# Power_Stage.net
KiCad netlist of a schematic drawn in Altium Designer
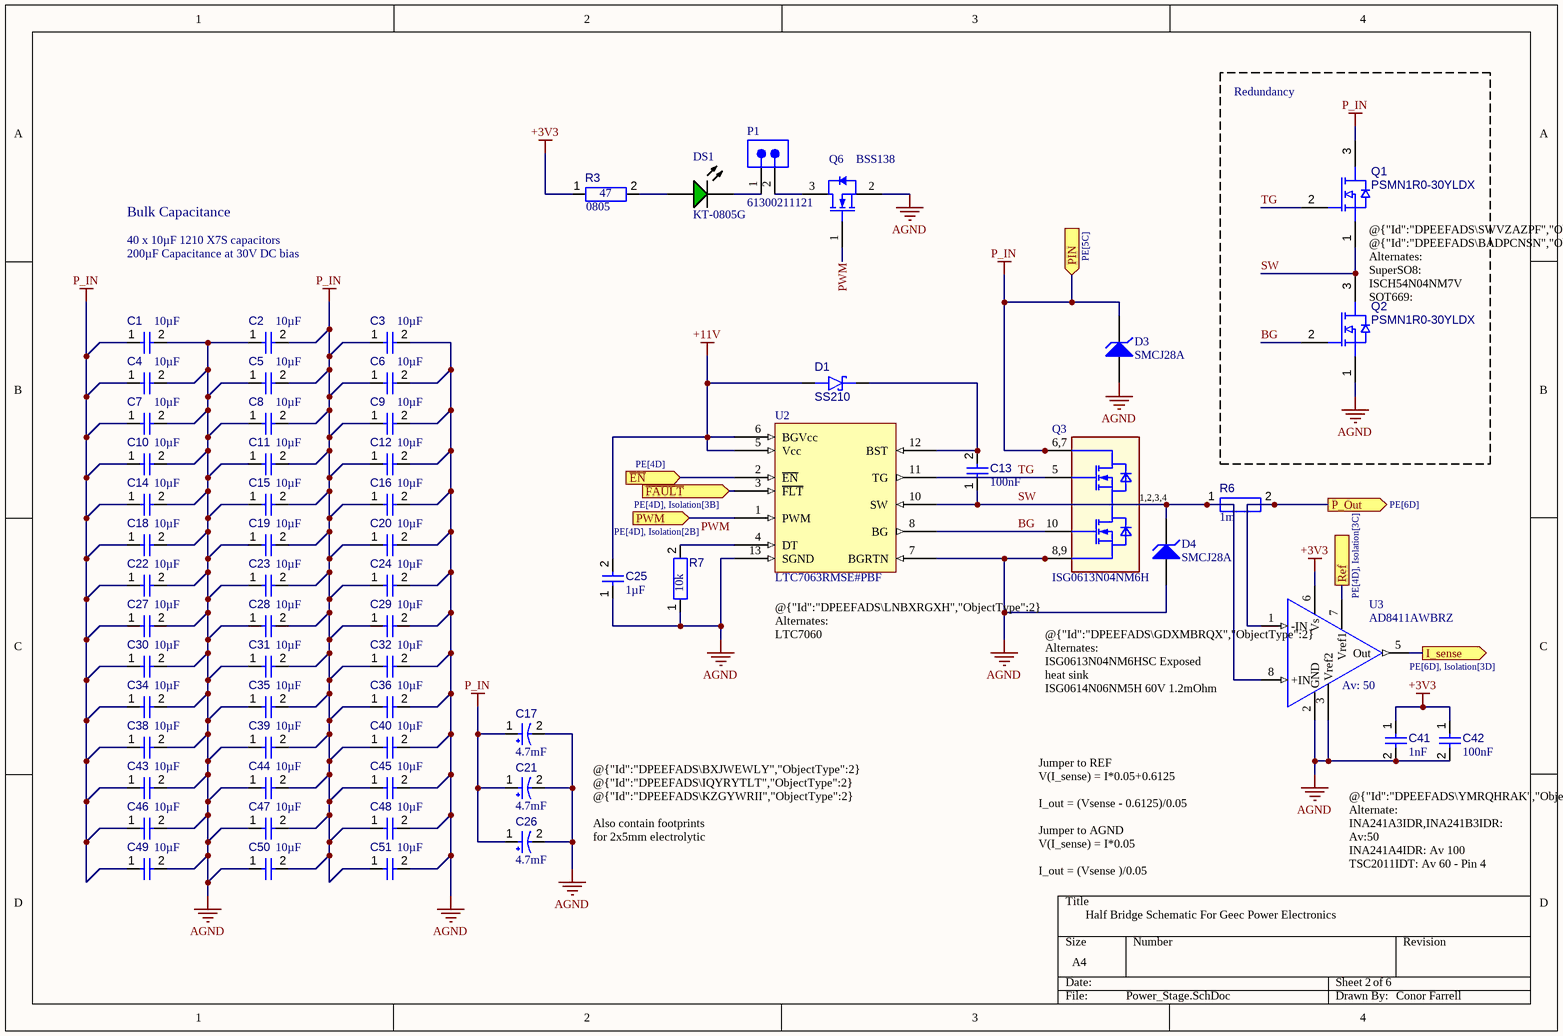
[diagram p0: Power_Stage.SchDoc]

(export (version "E")
  (design (tool "Eeschema 10.0.6"))
  (components
    (comp (ref "C1")
      (value "10µF")
      (footprint "FP-GCM32E-0_3-IPC_C")
      (description "50V 10uF X7S ±10% 1210 Multilayer Ceramic Capacitors MLCC - SMD/SMT ROHS")
      (fields (field (name "TOLERANCE") "10%") (field (name "Comment") "GCM32EC71H106KA03L"))
      (libsource (lib "University of Galway") (part "CAP-NP-2"))
    )
    (comp (ref "C2")
      (value "10µF")
      (footprint "FP-GCM32E-0_3-IPC_C")
      (description "50V 10uF X7S ±10% 1210 Multilayer Ceramic Capacitors MLCC - SMD/SMT ROHS")
      (fields (field (name "TOLERANCE") "10%") (field (name "Comment") "GCM32EC71H106KA03L"))
      (libsource (lib "University of Galway") (part "CAP-NP-2"))
    )
    (comp (ref "C3")
      (value "10µF")
      (footprint "FP-GCM32E-0_3-IPC_C")
      (description "50V 10uF X7S ±10% 1210 Multilayer Ceramic Capacitors MLCC - SMD/SMT ROHS")
      (fields (field (name "TOLERANCE") "10%") (field (name "Comment") "GCM32EC71H106KA03L"))
      (libsource (lib "University of Galway") (part "CAP-NP-2"))
    )
    (comp (ref "C4")
      (value "10µF")
      (footprint "FP-GCM32E-0_3-IPC_C")
      (description "50V 10uF X7S ±10% 1210 Multilayer Ceramic Capacitors MLCC - SMD/SMT ROHS")
      (fields (field (name "TOLERANCE") "10%") (field (name "Comment") "GCM32EC71H106KA03L"))
      (libsource (lib "University of Galway") (part "CAP-NP-2"))
    )
    (comp (ref "C5")
      (value "10µF")
      (footprint "FP-GCM32E-0_3-IPC_C")
      (description "50V 10uF X7S ±10% 1210 Multilayer Ceramic Capacitors MLCC - SMD/SMT ROHS")
      (fields (field (name "TOLERANCE") "10%") (field (name "Comment") "GCM32EC71H106KA03L"))
      (libsource (lib "University of Galway") (part "CAP-NP-2"))
    )
    (comp (ref "C6")
      (value "10µF")
      (footprint "FP-GCM32E-0_3-IPC_C")
      (description "50V 10uF X7S ±10% 1210 Multilayer Ceramic Capacitors MLCC - SMD/SMT ROHS")
      (fields (field (name "TOLERANCE") "10%") (field (name "Comment") "GCM32EC71H106KA03L"))
      (libsource (lib "University of Galway") (part "CAP-NP-2"))
    )
    (comp (ref "C7")
      (value "10µF")
      (footprint "FP-GCM32E-0_3-IPC_C")
      (description "50V 10uF X7S ±10% 1210 Multilayer Ceramic Capacitors MLCC - SMD/SMT ROHS")
      (fields (field (name "TOLERANCE") "10%") (field (name "Comment") "GCM32EC71H106KA03L"))
      (libsource (lib "University of Galway") (part "CAP-NP-2"))
    )
    (comp (ref "C8")
      (value "10µF")
      (footprint "FP-GCM32E-0_3-IPC_C")
      (description "50V 10uF X7S ±10% 1210 Multilayer Ceramic Capacitors MLCC - SMD/SMT ROHS")
      (fields (field (name "TOLERANCE") "10%") (field (name "Comment") "GCM32EC71H106KA03L"))
      (libsource (lib "University of Galway") (part "CAP-NP-2"))
    )
    (comp (ref "C9")
      (value "10µF")
      (footprint "FP-GCM32E-0_3-IPC_C")
      (description "50V 10uF X7S ±10% 1210 Multilayer Ceramic Capacitors MLCC - SMD/SMT ROHS")
      (fields (field (name "TOLERANCE") "10%") (field (name "Comment") "GCM32EC71H106KA03L"))
      (libsource (lib "University of Galway") (part "CAP-NP-2"))
    )
    (comp (ref "C10")
      (value "10µF")
      (footprint "FP-GCM32E-0_3-IPC_C")
      (description "50V 10uF X7S ±10% 1210 Multilayer Ceramic Capacitors MLCC - SMD/SMT ROHS")
      (fields (field (name "TOLERANCE") "10%") (field (name "Comment") "GCM32EC71H106KA03L"))
      (libsource (lib "University of Galway") (part "CAP-NP-2"))
    )
    (comp (ref "C11")
      (value "10µF")
      (footprint "FP-GCM32E-0_3-IPC_C")
      (description "50V 10uF X7S ±10% 1210 Multilayer Ceramic Capacitors MLCC - SMD/SMT ROHS")
      (fields (field (name "TOLERANCE") "10%") (field (name "Comment") "GCM32EC71H106KA03L"))
      (libsource (lib "University of Galway") (part "CAP-NP-2"))
    )
    (comp (ref "C12")
      (value "10µF")
      (footprint "FP-GCM32E-0_3-IPC_C")
      (description "50V 10uF X7S ±10% 1210 Multilayer Ceramic Capacitors MLCC - SMD/SMT ROHS")
      (fields (field (name "TOLERANCE") "10%") (field (name "Comment") "GCM32EC71H106KA03L"))
      (libsource (lib "University of Galway") (part "CAP-NP-2"))
    )
    (comp (ref "C13")
      (value "100nF")
      (footprint "CAPC3216X06N")
      (description "Ceramic Capacitor, Multilayer, Ceramic, 200V, 10% +Tol, 10% -Tol, X7R, 15% TC, 0.01uF, 1206")
      (fields (field (name "TOLERANCE") "10%") (field (name "Comment") "C1206C104K1RACTU"))
      (libsource (lib "University of Galway") (part "CAP-NP-2"))
    )
    (comp (ref "C14")
      (value "10µF")
      (footprint "FP-GCM32E-0_3-IPC_C")
      (description "50V 10uF X7S ±10% 1210 Multilayer Ceramic Capacitors MLCC - SMD/SMT ROHS")
      (fields (field (name "TOLERANCE") "10%") (field (name "Comment") "GCM32EC71H106KA03L"))
      (libsource (lib "University of Galway") (part "CAP-NP-2"))
    )
    (comp (ref "C15")
      (value "10µF")
      (footprint "FP-GCM32E-0_3-IPC_C")
      (description "50V 10uF X7S ±10% 1210 Multilayer Ceramic Capacitors MLCC - SMD/SMT ROHS")
      (fields (field (name "TOLERANCE") "10%") (field (name "Comment") "GCM32EC71H106KA03L"))
      (libsource (lib "University of Galway") (part "CAP-NP-2"))
    )
    (comp (ref "C16")
      (value "10µF")
      (footprint "FP-GCM32E-0_3-IPC_C")
      (description "50V 10uF X7S ±10% 1210 Multilayer Ceramic Capacitors MLCC - SMD/SMT ROHS")
      (fields (field (name "TOLERANCE") "10%") (field (name "Comment") "GCM32EC71H106KA03L"))
      (libsource (lib "University of Galway") (part "CAP-NP-2"))
    )
    (comp (ref "C17")
      (value "4.7mF")
      (footprint "UVR1J472MRD-Footprint-1")
      (description "Radial Can ALUMINUM ELECTROLYTIC CAPACITOR UVR 63V 4700muF ±20% 0.866Dia 22.00mm")
      (fields (field (name "TOLERANCE") "20%") (field (name "Comment") "UVR1J472MRD"))
      (libsource (lib "University of Galway") (part "CAP-P-2"))
    )
    (comp (ref "C18")
      (value "10µF")
      (footprint "FP-GCM32E-0_3-IPC_C")
      (description "50V 10uF X7S ±10% 1210 Multilayer Ceramic Capacitors MLCC - SMD/SMT ROHS")
      (fields (field (name "TOLERANCE") "10%") (field (name "Comment") "GCM32EC71H106KA03L"))
      (libsource (lib "University of Galway") (part "CAP-NP-2"))
    )
    (comp (ref "C19")
      (value "10µF")
      (footprint "FP-GCM32E-0_3-IPC_C")
      (description "50V 10uF X7S ±10% 1210 Multilayer Ceramic Capacitors MLCC - SMD/SMT ROHS")
      (fields (field (name "TOLERANCE") "10%") (field (name "Comment") "GCM32EC71H106KA03L"))
      (libsource (lib "University of Galway") (part "CAP-NP-2"))
    )
    (comp (ref "C20")
      (value "10µF")
      (footprint "FP-GCM32E-0_3-IPC_C")
      (description "50V 10uF X7S ±10% 1210 Multilayer Ceramic Capacitors MLCC - SMD/SMT ROHS")
      (fields (field (name "TOLERANCE") "10%") (field (name "Comment") "GCM32EC71H106KA03L"))
      (libsource (lib "University of Galway") (part "CAP-NP-2"))
    )
    (comp (ref "C21")
      (value "4.7mF")
      (footprint "UVR1J472MRD-Footprint-1")
      (description "Radial Can ALUMINUM ELECTROLYTIC CAPACITOR UVR 63V 4700muF ±20% 0.866Dia 22.00mm")
      (fields (field (name "TOLERANCE") "20%") (field (name "Comment") "UVR1J472MRD"))
      (libsource (lib "University of Galway") (part "CAP-P-2"))
    )
    (comp (ref "C22")
      (value "10µF")
      (footprint "FP-GCM32E-0_3-IPC_C")
      (description "50V 10uF X7S ±10% 1210 Multilayer Ceramic Capacitors MLCC - SMD/SMT ROHS")
      (fields (field (name "TOLERANCE") "10%") (field (name "Comment") "GCM32EC71H106KA03L"))
      (libsource (lib "University of Galway") (part "CAP-NP-2"))
    )
    (comp (ref "C23")
      (value "10µF")
      (footprint "FP-GCM32E-0_3-IPC_C")
      (description "50V 10uF X7S ±10% 1210 Multilayer Ceramic Capacitors MLCC - SMD/SMT ROHS")
      (fields (field (name "TOLERANCE") "10%") (field (name "Comment") "GCM32EC71H106KA03L"))
      (libsource (lib "University of Galway") (part "CAP-NP-2"))
    )
    (comp (ref "C24")
      (value "10µF")
      (footprint "FP-GCM32E-0_3-IPC_C")
      (description "50V 10uF X7S ±10% 1210 Multilayer Ceramic Capacitors MLCC - SMD/SMT ROHS")
      (fields (field (name "TOLERANCE") "10%") (field (name "Comment") "GCM32EC71H106KA03L"))
      (libsource (lib "University of Galway") (part "CAP-NP-2"))
    )
    (comp (ref "C25")
      (value "1µF")
      (footprint "CAPC3216X180X20ML20")
      (fields (field (name "TOLERANCE") "10%") (field (name "Comment") "CL31B105KBHNNNE"))
      (libsource (lib "University of Galway") (part "CAP-NP-2"))
    )
    (comp (ref "C26")
      (value "4.7mF")
      (footprint "UVR1J472MRD-Footprint-1")
      (description "Radial Can ALUMINUM ELECTROLYTIC CAPACITOR UVR 63V 4700muF ±20% 0.866Dia 22.00mm")
      (fields (field (name "TOLERANCE") "20%") (field (name "Comment") "UVR1J472MRD"))
      (libsource (lib "University of Galway") (part "CAP-P-2"))
    )
    (comp (ref "C27")
      (value "10µF")
      (footprint "FP-GCM32E-0_3-IPC_C")
      (description "50V 10uF X7S ±10% 1210 Multilayer Ceramic Capacitors MLCC - SMD/SMT ROHS")
      (fields (field (name "TOLERANCE") "10%") (field (name "Comment") "GCM32EC71H106KA03L"))
      (libsource (lib "University of Galway") (part "CAP-NP-2"))
    )
    (comp (ref "C28")
      (value "10µF")
      (footprint "FP-GCM32E-0_3-IPC_C")
      (description "50V 10uF X7S ±10% 1210 Multilayer Ceramic Capacitors MLCC - SMD/SMT ROHS")
      (fields (field (name "TOLERANCE") "10%") (field (name "Comment") "GCM32EC71H106KA03L"))
      (libsource (lib "University of Galway") (part "CAP-NP-2"))
    )
    (comp (ref "C29")
      (value "10µF")
      (footprint "FP-GCM32E-0_3-IPC_C")
      (description "50V 10uF X7S ±10% 1210 Multilayer Ceramic Capacitors MLCC - SMD/SMT ROHS")
      (fields (field (name "TOLERANCE") "10%") (field (name "Comment") "GCM32EC71H106KA03L"))
      (libsource (lib "University of Galway") (part "CAP-NP-2"))
    )
    (comp (ref "C30")
      (value "10µF")
      (footprint "FP-GCM32E-0_3-IPC_C")
      (description "50V 10uF X7S ±10% 1210 Multilayer Ceramic Capacitors MLCC - SMD/SMT ROHS")
      (fields (field (name "TOLERANCE") "10%") (field (name "Comment") "GCM32EC71H106KA03L"))
      (libsource (lib "University of Galway") (part "CAP-NP-2"))
    )
    (comp (ref "C31")
      (value "10µF")
      (footprint "FP-GCM32E-0_3-IPC_C")
      (description "50V 10uF X7S ±10% 1210 Multilayer Ceramic Capacitors MLCC - SMD/SMT ROHS")
      (fields (field (name "TOLERANCE") "10%") (field (name "Comment") "GCM32EC71H106KA03L"))
      (libsource (lib "University of Galway") (part "CAP-NP-2"))
    )
    (comp (ref "C32")
      (value "10µF")
      (footprint "FP-GCM32E-0_3-IPC_C")
      (description "50V 10uF X7S ±10% 1210 Multilayer Ceramic Capacitors MLCC - SMD/SMT ROHS")
      (fields (field (name "TOLERANCE") "10%") (field (name "Comment") "GCM32EC71H106KA03L"))
      (libsource (lib "University of Galway") (part "CAP-NP-2"))
    )
    (comp (ref "C34")
      (value "10µF")
      (footprint "FP-GCM32E-0_3-IPC_C")
      (description "50V 10uF X7S ±10% 1210 Multilayer Ceramic Capacitors MLCC - SMD/SMT ROHS")
      (fields (field (name "TOLERANCE") "10%") (field (name "Comment") "GCM32EC71H106KA03L"))
      (libsource (lib "University of Galway") (part "CAP-NP-2"))
    )
    (comp (ref "C35")
      (value "10µF")
      (footprint "FP-GCM32E-0_3-IPC_C")
      (description "50V 10uF X7S ±10% 1210 Multilayer Ceramic Capacitors MLCC - SMD/SMT ROHS")
      (fields (field (name "TOLERANCE") "10%") (field (name "Comment") "GCM32EC71H106KA03L"))
      (libsource (lib "University of Galway") (part "CAP-NP-2"))
    )
    (comp (ref "C36")
      (value "10µF")
      (footprint "FP-GCM32E-0_3-IPC_C")
      (description "50V 10uF X7S ±10% 1210 Multilayer Ceramic Capacitors MLCC - SMD/SMT ROHS")
      (fields (field (name "TOLERANCE") "10%") (field (name "Comment") "GCM32EC71H106KA03L"))
      (libsource (lib "University of Galway") (part "CAP-NP-2"))
    )
    (comp (ref "C38")
      (value "10µF")
      (footprint "FP-GCM32E-0_3-IPC_C")
      (description "50V 10uF X7S ±10% 1210 Multilayer Ceramic Capacitors MLCC - SMD/SMT ROHS")
      (fields (field (name "TOLERANCE") "10%") (field (name "Comment") "GCM32EC71H106KA03L"))
      (libsource (lib "University of Galway") (part "CAP-NP-2"))
    )
    (comp (ref "C39")
      (value "10µF")
      (footprint "FP-GCM32E-0_3-IPC_C")
      (description "50V 10uF X7S ±10% 1210 Multilayer Ceramic Capacitors MLCC - SMD/SMT ROHS")
      (fields (field (name "TOLERANCE") "10%") (field (name "Comment") "GCM32EC71H106KA03L"))
      (libsource (lib "University of Galway") (part "CAP-NP-2"))
    )
    (comp (ref "C40")
      (value "10µF")
      (footprint "FP-GCM32E-0_3-IPC_C")
      (description "50V 10uF X7S ±10% 1210 Multilayer Ceramic Capacitors MLCC - SMD/SMT ROHS")
      (fields (field (name "TOLERANCE") "10%") (field (name "Comment") "GCM32EC71H106KA03L"))
      (libsource (lib "University of Galway") (part "CAP-NP-2"))
    )
    (comp (ref "C41")
      (value "1nF")
      (footprint "FP-CL31-IPC_A")
      (fields (field (name "TOLERANCE") "10%") (field (name "Comment") "CL31B102KGFNNNE"))
      (libsource (lib "University of Galway") (part "CAP-NP-2"))
    )
    (comp (ref "C42")
      (value "100nF")
      (footprint "CAPC3216X06N")
      (description "Ceramic Capacitor, Multilayer, Ceramic, 200V, 10% +Tol, 10% -Tol, X7R, 15% TC, 0.01uF, 1206")
      (fields (field (name "TOLERANCE") "10%") (field (name "Comment") "C1206C104K1RACTU"))
      (libsource (lib "University of Galway") (part "CAP-NP-2"))
    )
    (comp (ref "C43")
      (value "10µF")
      (footprint "FP-GCM32E-0_3-IPC_C")
      (description "50V 10uF X7S ±10% 1210 Multilayer Ceramic Capacitors MLCC - SMD/SMT ROHS")
      (fields (field (name "TOLERANCE") "10%") (field (name "Comment") "GCM32EC71H106KA03L"))
      (libsource (lib "University of Galway") (part "CAP-NP-2"))
    )
    (comp (ref "C44")
      (value "10µF")
      (footprint "FP-GCM32E-0_3-IPC_C")
      (description "50V 10uF X7S ±10% 1210 Multilayer Ceramic Capacitors MLCC - SMD/SMT ROHS")
      (fields (field (name "TOLERANCE") "10%") (field (name "Comment") "GCM32EC71H106KA03L"))
      (libsource (lib "University of Galway") (part "CAP-NP-2"))
    )
    (comp (ref "C45")
      (value "10µF")
      (footprint "FP-GCM32E-0_3-IPC_C")
      (description "50V 10uF X7S ±10% 1210 Multilayer Ceramic Capacitors MLCC - SMD/SMT ROHS")
      (fields (field (name "TOLERANCE") "10%") (field (name "Comment") "GCM32EC71H106KA03L"))
      (libsource (lib "University of Galway") (part "CAP-NP-2"))
    )
    (comp (ref "C46")
      (value "10µF")
      (footprint "FP-GCM32E-0_3-IPC_C")
      (description "50V 10uF X7S ±10% 1210 Multilayer Ceramic Capacitors MLCC - SMD/SMT ROHS")
      (fields (field (name "TOLERANCE") "10%") (field (name "Comment") "GCM32EC71H106KA03L"))
      (libsource (lib "University of Galway") (part "CAP-NP-2"))
    )
    (comp (ref "C47")
      (value "10µF")
      (footprint "FP-GCM32E-0_3-IPC_C")
      (description "50V 10uF X7S ±10% 1210 Multilayer Ceramic Capacitors MLCC - SMD/SMT ROHS")
      (fields (field (name "TOLERANCE") "10%") (field (name "Comment") "GCM32EC71H106KA03L"))
      (libsource (lib "University of Galway") (part "CAP-NP-2"))
    )
    (comp (ref "C48")
      (value "10µF")
      (footprint "FP-GCM32E-0_3-IPC_C")
      (description "50V 10uF X7S ±10% 1210 Multilayer Ceramic Capacitors MLCC - SMD/SMT ROHS")
      (fields (field (name "TOLERANCE") "10%") (field (name "Comment") "GCM32EC71H106KA03L"))
      (libsource (lib "University of Galway") (part "CAP-NP-2"))
    )
    (comp (ref "C49")
      (value "10µF")
      (footprint "FP-GCM32E-0_3-IPC_C")
      (description "50V 10uF X7S ±10% 1210 Multilayer Ceramic Capacitors MLCC - SMD/SMT ROHS")
      (fields (field (name "TOLERANCE") "10%") (field (name "Comment") "GCM32EC71H106KA03L"))
      (libsource (lib "University of Galway") (part "CAP-NP-2"))
    )
    (comp (ref "C50")
      (value "10µF")
      (footprint "FP-GCM32E-0_3-IPC_C")
      (description "50V 10uF X7S ±10% 1210 Multilayer Ceramic Capacitors MLCC - SMD/SMT ROHS")
      (fields (field (name "TOLERANCE") "10%") (field (name "Comment") "GCM32EC71H106KA03L"))
      (libsource (lib "University of Galway") (part "CAP-NP-2"))
    )
    (comp (ref "C51")
      (value "10µF")
      (footprint "FP-GCM32E-0_3-IPC_C")
      (description "50V 10uF X7S ±10% 1210 Multilayer Ceramic Capacitors MLCC - SMD/SMT ROHS")
      (fields (field (name "TOLERANCE") "10%") (field (name "Comment") "GCM32EC71H106KA03L"))
      (libsource (lib "University of Galway") (part "CAP-NP-2"))
    )
    (comp (ref "D1")
      (value "SS210")
      (footprint "DIOM4226X24N")
      (description "Rectifier Diode, Schottky, 1 Phase, 1 Element, 2A, 100V V(RRM), Silicon, DO-214AA")
      (libsource (lib "University of Galway") (part "DIODE-SKY-2"))
    )
    (comp (ref "D3")
      (value "SMCJ28A")
      (footprint "FAIR-DO-214AB-2_V")
      (description "SMCJ Series 45.4 V 1.5 kW Surface Mount Uni-Directional TVS Diode - DO-214AB")
      (libsource (lib "University of Galway") (part "DZEN-AK-2"))
    )
    (comp (ref "D4")
      (value "SMCJ28A")
      (footprint "FAIR-DO-214AB-2_V")
      (description "SMCJ Series 45.4 V 1.5 kW Surface Mount Uni-Directional TVS Diode - DO-214AB")
      (libsource (lib "University of Galway") (part "DZEN-AK-2"))
    )
    (comp (ref "DS1")
      (value "KT-0805G")
      (footprint "WL-SMCW_0805_150080xx75000")
      (libsource (lib "University of Galway") (part "LED-GREEN-AK-2"))
    )
    (comp (ref "P1")
      (value "61300211121")
      (footprint "61300211121")
      (description "WR-PHD Pin Header, THT, Vertical, pitch 2.54mm, 1 Row, 2P")
      (fields (field (name "MANUFACTURER") "Wurth Elektronik"))
      (libsource (lib "University of Galway") (part "62000211121"))
    )
    (comp (ref "Q1")
      (value "PSMN1R0-30YLDX")
      (footprint "NXP-SOT669_L")
      (description "N-channel Logic Level MOSFET, 30 V, 300 A, -55 to 175 degC, 5-Pin SOT669, RoHS, Tape and Reel")
      (libsource (lib "University of Galway") (part "CMP-00089-6"))
    )
    (comp (ref "Q2")
      (value "PSMN1R0-30YLDX")
      (footprint "NXP-SOT669_L")
      (description "N-channel Logic Level MOSFET, 30 V, 300 A, -55 to 175 degC, 5-Pin SOT669, RoHS, Tape and Reel")
      (libsource (lib "University of Galway") (part "CMP-00089-6"))
    )
    (comp (ref "Q3")
      (value "ISG0613N04NM6H")
      (footprint "IFX-PG-VITFN-10-1-V")
      (fields (field (name "MANUFACTURER") "Infineon Technologies"))
      (libsource (lib "University of Galway") (part "ISG0613N04NM6H"))
    )
    (comp (ref "Q6")
      (value "BSS138")
      (footprint "FAIR-SOT23-3_V")
      (fields (field (name "MANUFACTURER") "Fairchild") (field (name "POWER") "360mW"))
      (libsource (lib "University of Galway") (part "NEMOS-GSD-3"))
    )
    (comp (ref "R3")
      (value "47")
      (footprint "RESC2013X70X40ML20T20")
      (description "Thick Film Resistors - SMD RMC 0805 1/8W 1% T/R-5000")
      (fields
        (field (name "CASE/PACKAGE") "0805")
        (field (name "POWER") "125mW")
        (field (name "Comment") "0805W8F470JT5E")
      )
      (libsource (lib "University of Galway") (part "RES-2"))
    )
    (comp (ref "R6")
      (value "1m")
      (footprint "RESC6331X09N")
      (description "Fixed Resistor, Metal Strip, 5W, 1ohm, 0.0707V, 1% +/-Tol, 100ppm/Cel, Surface Mount, 2512")
      (fields (field (name "TOLERANCE") "1%") (field (name "Comment") "CHSA2512R0010F"))
      (libsource (lib "University of Galway") (part "RES-2"))
    )
    (comp (ref "R7")
      (value "10k")
      (footprint "RESC3216X60X45ML15T20")
      (description "Res Thick Film 1206 10K Ohm 1% 0.25W(1/4W) ±100ppm/C Pad SMD T/R")
      (fields (field (name "Comment") "1206W4F1002T5E"))
      (libsource (lib "University of Galway") (part "RES-2"))
    )
    (comp (ref "U2")
      (value "LTC7063RMSE#PBF")
      (footprint "TSOP65P490X110_HS-13N")
      (description "Driver 6A 2-OUT High Side/Low Side Half Brdg Inv/Non-Inv 12-Pin MSOP EP Tube")
      (libsource (lib "University of Galway") (part "LTC7063RMSE#PBF-Symbol-1"))
    )
    (comp (ref "U3")
      (value "AD8411AWBRZ")
      (footprint "SOIC127P600X175-8N")
      (description "SP Amp Current Sense Amp Single 5.5V 8-Pin SOIC N Tube Automotive AEC-Q100")
      (libsource (lib "University of Galway") (part "AD8411AWBRZ-Symbol-1"))
    )
  )
  (nets
    (net (code "1") (name "+3V3") (class "Default")
      (node (ref "C41") (pin "1") (pinfunction "1_1") (pintype "passive"))
      (node (ref "C42") (pin "1") (pinfunction "1_1") (pintype "passive"))
      (node (ref "R3") (pin "1") (pinfunction "1_1") (pintype "passive"))
      (node (ref "U3") (pin "6") (pinfunction "Vs_6") (pintype "passive"))
    )
    (net (code "2") (name "+11V") (class "Default")
      (node (ref "C25") (pin "2") (pinfunction "2_2") (pintype "passive"))
      (node (ref "D1") (pin "2") (pinfunction "A_2") (pintype "passive"))
      (node (ref "U2") (pin "5") (pinfunction "Vcc_5") (pintype "input"))
      (node (ref "U2") (pin "6") (pinfunction "BGVcc_6") (pintype "input"))
    )
    (net (code "3") (name "/BG") (class "Default")
      (node (ref "Q2") (pin "2") (pinfunction "G_2") (pintype "passive"))
      (node (ref "Q3") (pin "10") (pinfunction "G2_10") (pintype "passive"))
      (node (ref "U2") (pin "8") (pinfunction "BG_8") (pintype "output"))
    )
    (net (code "4") (name "/I_sense") (class "Default")
      (node (ref "U3") (pin "5") (pinfunction "Out_5") (pintype "output"))
    )
    (net (code "5") (name "/PWM") (class "Default")
      (node (ref "Q6") (pin "1") (pinfunction "G_1") (pintype "passive"))
      (node (ref "U2") (pin "1") (pinfunction "PWM_1") (pintype "input"))
    )
    (net (code "6") (name "/P_Out") (class "Default")
      (node (ref "R6") (pin "2") (pinfunction "2_2") (pintype "passive"))
      (node (ref "U3") (pin "1") (pinfunction "-IN_1") (pintype "input"))
    )
    (net (code "7") (name "/Ref") (class "Default")
      (node (ref "U3") (pin "7") (pinfunction "Vref1_7") (pintype "passive"))
    )
    (net (code "8") (name "/SW") (class "Default")
      (node (ref "C13") (pin "1") (pinfunction "1_1") (pintype "passive"))
      (node (ref "D4") (pin "2") (pinfunction "K_2") (pintype "passive"))
      (node (ref "Q1") (pin "1") (pinfunction "S_1") (pintype "passive"))
      (node (ref "Q2") (pin "3") (pinfunction "D_3") (pintype "passive"))
      (node (ref "Q3") (pin "1") (pinfunction "S1_1") (pintype "passive"))
      (node (ref "Q3") (pin "2") (pinfunction "S2_2") (pintype "passive"))
      (node (ref "Q3") (pin "3") (pinfunction "D1_3") (pintype "passive"))
      (node (ref "Q3") (pin "4") (pinfunction "D2_4") (pintype "passive"))
      (node (ref "R6") (pin "1") (pinfunction "1_1") (pintype "passive"))
      (node (ref "U2") (pin "10") (pinfunction "SW_10") (pintype "input"))
      (node (ref "U3") (pin "8") (pinfunction "+IN_8") (pintype "input"))
    )
    (net (code "9") (name "/TG") (class "Default")
      (node (ref "Q1") (pin "2") (pinfunction "G_2") (pintype "passive"))
      (node (ref "Q3") (pin "5") (pinfunction "G1_5") (pintype "passive"))
      (node (ref "U2") (pin "11") (pinfunction "TG_11") (pintype "output"))
    )
    (net (code "10") (name "/~{EN}") (class "Default")
      (node (ref "U2") (pin "2") (pinfunction "~{EN}_2") (pintype "input"))
    )
    (net (code "11") (name "/~{FAULT}") (class "Default")
      (node (ref "U2") (pin "3") (pinfunction "~{FLT}_3") (pintype "input"))
    )
    (net (code "12") (name "AGND") (class "Default")
      (node (ref "C1") (pin "2") (pinfunction "2_2") (pintype "passive"))
      (node (ref "C10") (pin "2") (pinfunction "2_2") (pintype "passive"))
      (node (ref "C11") (pin "1") (pinfunction "1_1") (pintype "passive"))
      (node (ref "C12") (pin "2") (pinfunction "2_2") (pintype "passive"))
      (node (ref "C14") (pin "2") (pinfunction "2_2") (pintype "passive"))
      (node (ref "C15") (pin "1") (pinfunction "1_1") (pintype "passive"))
      (node (ref "C16") (pin "2") (pinfunction "2_2") (pintype "passive"))
      (node (ref "C17") (pin "2") (pinfunction "2_2") (pintype "passive"))
      (node (ref "C18") (pin "2") (pinfunction "2_2") (pintype "passive"))
      (node (ref "C19") (pin "1") (pinfunction "1_1") (pintype "passive"))
      (node (ref "C2") (pin "1") (pinfunction "1_1") (pintype "passive"))
      (node (ref "C20") (pin "2") (pinfunction "2_2") (pintype "passive"))
      (node (ref "C21") (pin "2") (pinfunction "2_2") (pintype "passive"))
      (node (ref "C22") (pin "2") (pinfunction "2_2") (pintype "passive"))
      (node (ref "C23") (pin "1") (pinfunction "1_1") (pintype "passive"))
      (node (ref "C24") (pin "2") (pinfunction "2_2") (pintype "passive"))
      (node (ref "C25") (pin "1") (pinfunction "1_1") (pintype "passive"))
      (node (ref "C26") (pin "2") (pinfunction "2_2") (pintype "passive"))
      (node (ref "C27") (pin "2") (pinfunction "2_2") (pintype "passive"))
      (node (ref "C28") (pin "1") (pinfunction "1_1") (pintype "passive"))
      (node (ref "C29") (pin "2") (pinfunction "2_2") (pintype "passive"))
      (node (ref "C3") (pin "2") (pinfunction "2_2") (pintype "passive"))
      (node (ref "C30") (pin "2") (pinfunction "2_2") (pintype "passive"))
      (node (ref "C31") (pin "1") (pinfunction "1_1") (pintype "passive"))
      (node (ref "C32") (pin "2") (pinfunction "2_2") (pintype "passive"))
      (node (ref "C34") (pin "2") (pinfunction "2_2") (pintype "passive"))
      (node (ref "C35") (pin "1") (pinfunction "1_1") (pintype "passive"))
      (node (ref "C36") (pin "2") (pinfunction "2_2") (pintype "passive"))
      (node (ref "C38") (pin "2") (pinfunction "2_2") (pintype "passive"))
      (node (ref "C39") (pin "1") (pinfunction "1_1") (pintype "passive"))
      (node (ref "C4") (pin "2") (pinfunction "2_2") (pintype "passive"))
      (node (ref "C40") (pin "2") (pinfunction "2_2") (pintype "passive"))
      (node (ref "C41") (pin "2") (pinfunction "2_2") (pintype "passive"))
      (node (ref "C42") (pin "2") (pinfunction "2_2") (pintype "passive"))
      (node (ref "C43") (pin "2") (pinfunction "2_2") (pintype "passive"))
      (node (ref "C44") (pin "1") (pinfunction "1_1") (pintype "passive"))
      (node (ref "C45") (pin "2") (pinfunction "2_2") (pintype "passive"))
      (node (ref "C46") (pin "2") (pinfunction "2_2") (pintype "passive"))
      (node (ref "C47") (pin "1") (pinfunction "1_1") (pintype "passive"))
      (node (ref "C48") (pin "2") (pinfunction "2_2") (pintype "passive"))
      (node (ref "C49") (pin "2") (pinfunction "2_2") (pintype "passive"))
      (node (ref "C5") (pin "1") (pinfunction "1_1") (pintype "passive"))
      (node (ref "C50") (pin "1") (pinfunction "1_1") (pintype "passive"))
      (node (ref "C51") (pin "2") (pinfunction "2_2") (pintype "passive"))
      (node (ref "C6") (pin "2") (pinfunction "2_2") (pintype "passive"))
      (node (ref "C7") (pin "2") (pinfunction "2_2") (pintype "passive"))
      (node (ref "C8") (pin "1") (pinfunction "1_1") (pintype "passive"))
      (node (ref "C9") (pin "2") (pinfunction "2_2") (pintype "passive"))
      (node (ref "D3") (pin "1") (pinfunction "A_1") (pintype "passive"))
      (node (ref "D4") (pin "1") (pinfunction "A_1") (pintype "passive"))
      (node (ref "Q2") (pin "1") (pinfunction "S_1") (pintype "passive"))
      (node (ref "Q3") (pin "8") (pinfunction "S3_8") (pintype "passive"))
      (node (ref "Q3") (pin "9") (pinfunction "S4_9") (pintype "passive"))
      (node (ref "Q6") (pin "2") (pinfunction "S_2") (pintype "passive"))
      (node (ref "R7") (pin "1") (pinfunction "1_1") (pintype "passive"))
      (node (ref "U2") (pin "13") (pinfunction "SGND_13") (pintype "input"))
      (node (ref "U2") (pin "7") (pinfunction "BGRTN_7") (pintype "input"))
      (node (ref "U3") (pin "2") (pinfunction "GND_2") (pintype "passive"))
      (node (ref "U3") (pin "3") (pinfunction "Vref2_3") (pintype "passive"))
    )
    (net (code "13") (name "Net-(D1-K)") (class "Default")
      (node (ref "C13") (pin "2") (pinfunction "2_2") (pintype "passive"))
      (node (ref "D1") (pin "1") (pinfunction "K_1") (pintype "passive"))
      (node (ref "U2") (pin "12") (pinfunction "BST_12") (pintype "input"))
    )
    (net (code "14") (name "Net-(DS1-A)") (class "Default")
      (node (ref "DS1") (pin "1") (pinfunction "A_1") (pintype "passive"))
      (node (ref "R3") (pin "2") (pinfunction "2_2") (pintype "passive"))
    )
    (net (code "15") (name "Net-(DS1-K)") (class "Default")
      (node (ref "DS1") (pin "2") (pinfunction "K_2") (pintype "passive"))
      (node (ref "P1") (pin "1") (pinfunction "1_1") (pintype "passive"))
    )
    (net (code "16") (name "Net-(Q6-D)") (class "Default")
      (node (ref "P1") (pin "2") (pinfunction "2_2") (pintype "passive"))
      (node (ref "Q6") (pin "3") (pinfunction "D_3") (pintype "passive"))
    )
    (net (code "17") (name "Net-(U2-DT)") (class "Default")
      (node (ref "R7") (pin "2") (pinfunction "2_2") (pintype "passive"))
      (node (ref "U2") (pin "4") (pinfunction "DT_4") (pintype "input"))
    )
    (net (code "18") (name "P_IN") (class "Default")
      (node (ref "C1") (pin "1") (pinfunction "1_1") (pintype "passive"))
      (node (ref "C10") (pin "1") (pinfunction "1_1") (pintype "passive"))
      (node (ref "C11") (pin "2") (pinfunction "2_2") (pintype "passive"))
      (node (ref "C12") (pin "1") (pinfunction "1_1") (pintype "passive"))
      (node (ref "C14") (pin "1") (pinfunction "1_1") (pintype "passive"))
      (node (ref "C15") (pin "2") (pinfunction "2_2") (pintype "passive"))
      (node (ref "C16") (pin "1") (pinfunction "1_1") (pintype "passive"))
      (node (ref "C17") (pin "1") (pinfunction "1_1") (pintype "passive"))
      (node (ref "C18") (pin "1") (pinfunction "1_1") (pintype "passive"))
      (node (ref "C19") (pin "2") (pinfunction "2_2") (pintype "passive"))
      (node (ref "C2") (pin "2") (pinfunction "2_2") (pintype "passive"))
      (node (ref "C20") (pin "1") (pinfunction "1_1") (pintype "passive"))
      (node (ref "C21") (pin "1") (pinfunction "1_1") (pintype "passive"))
      (node (ref "C22") (pin "1") (pinfunction "1_1") (pintype "passive"))
      (node (ref "C23") (pin "2") (pinfunction "2_2") (pintype "passive"))
      (node (ref "C24") (pin "1") (pinfunction "1_1") (pintype "passive"))
      (node (ref "C26") (pin "1") (pinfunction "1_1") (pintype "passive"))
      (node (ref "C27") (pin "1") (pinfunction "1_1") (pintype "passive"))
      (node (ref "C28") (pin "2") (pinfunction "2_2") (pintype "passive"))
      (node (ref "C29") (pin "1") (pinfunction "1_1") (pintype "passive"))
      (node (ref "C3") (pin "1") (pinfunction "1_1") (pintype "passive"))
      (node (ref "C30") (pin "1") (pinfunction "1_1") (pintype "passive"))
      (node (ref "C31") (pin "2") (pinfunction "2_2") (pintype "passive"))
      (node (ref "C32") (pin "1") (pinfunction "1_1") (pintype "passive"))
      (node (ref "C34") (pin "1") (pinfunction "1_1") (pintype "passive"))
      (node (ref "C35") (pin "2") (pinfunction "2_2") (pintype "passive"))
      (node (ref "C36") (pin "1") (pinfunction "1_1") (pintype "passive"))
      (node (ref "C38") (pin "1") (pinfunction "1_1") (pintype "passive"))
      (node (ref "C39") (pin "2") (pinfunction "2_2") (pintype "passive"))
      (node (ref "C4") (pin "1") (pinfunction "1_1") (pintype "passive"))
      (node (ref "C40") (pin "1") (pinfunction "1_1") (pintype "passive"))
      (node (ref "C43") (pin "1") (pinfunction "1_1") (pintype "passive"))
      (node (ref "C44") (pin "2") (pinfunction "2_2") (pintype "passive"))
      (node (ref "C45") (pin "1") (pinfunction "1_1") (pintype "passive"))
      (node (ref "C46") (pin "1") (pinfunction "1_1") (pintype "passive"))
      (node (ref "C47") (pin "2") (pinfunction "2_2") (pintype "passive"))
      (node (ref "C48") (pin "1") (pinfunction "1_1") (pintype "passive"))
      (node (ref "C49") (pin "1") (pinfunction "1_1") (pintype "passive"))
      (node (ref "C5") (pin "2") (pinfunction "2_2") (pintype "passive"))
      (node (ref "C50") (pin "2") (pinfunction "2_2") (pintype "passive"))
      (node (ref "C51") (pin "1") (pinfunction "1_1") (pintype "passive"))
      (node (ref "C6") (pin "1") (pinfunction "1_1") (pintype "passive"))
      (node (ref "C7") (pin "1") (pinfunction "1_1") (pintype "passive"))
      (node (ref "C8") (pin "2") (pinfunction "2_2") (pintype "passive"))
      (node (ref "C9") (pin "1") (pinfunction "1_1") (pintype "passive"))
      (node (ref "D3") (pin "2") (pinfunction "K_2") (pintype "passive"))
      (node (ref "Q1") (pin "3") (pinfunction "D_3") (pintype "passive"))
      (node (ref "Q3") (pin "6") (pinfunction "D3_6") (pintype "passive"))
      (node (ref "Q3") (pin "7") (pinfunction "D4_7") (pintype "passive"))
    )
  )
)
